# DSP_FPGA.net
KiCad netlist of a schematic drawn in Altium Designer
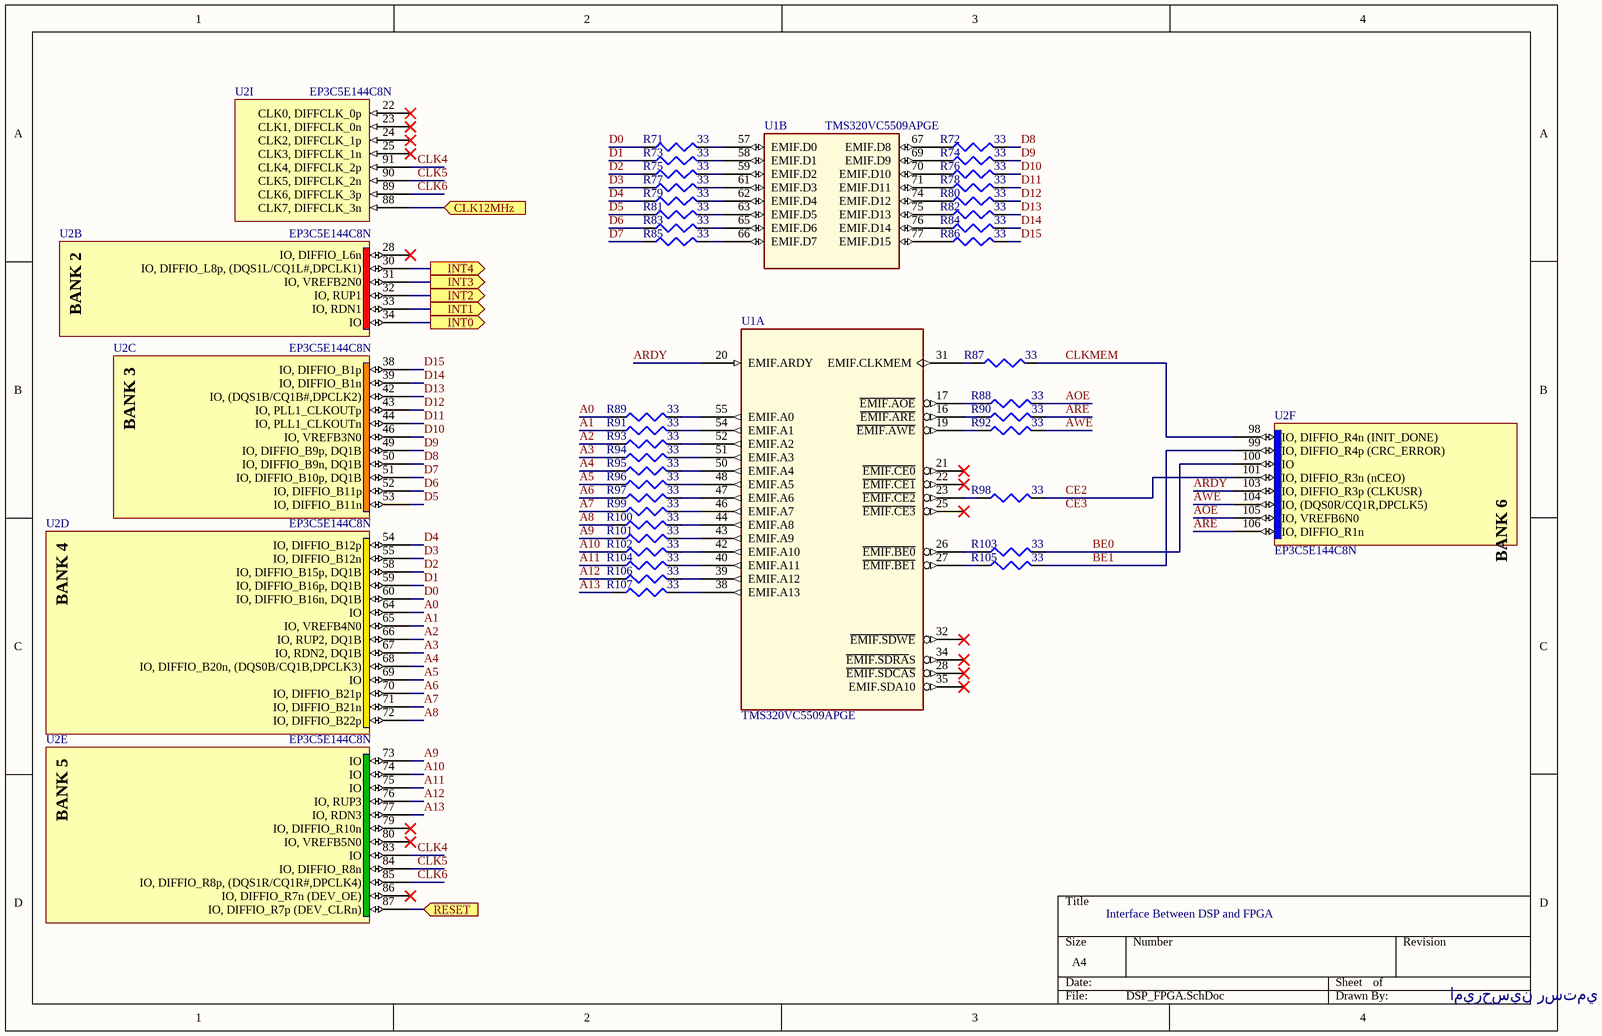
[diagram p0: DSP_FPGA.SchDoc]

(export (version "E")
  (design (tool "Eeschema 10.0.6"))
  (components
    (comp (ref "R71")
      (value "33")
      (footprint "J1-0603")
      (description "Resistor")
      (fields (field (name "PUBLISHER") "Altium Limited"))
      (libsource (lib "Miscellaneous Devices") (part "Res3"))
    )
    (comp (ref "R72")
      (value "33")
      (footprint "J1-0603")
      (description "Resistor")
      (fields (field (name "PUBLISHER") "Altium Limited"))
      (libsource (lib "Miscellaneous Devices") (part "Res3"))
    )
    (comp (ref "R73")
      (value "33")
      (footprint "J1-0603")
      (description "Resistor")
      (fields (field (name "PUBLISHER") "Altium Limited"))
      (libsource (lib "Miscellaneous Devices") (part "Res3"))
    )
    (comp (ref "R74")
      (value "33")
      (footprint "J1-0603")
      (description "Resistor")
      (fields (field (name "PUBLISHER") "Altium Limited"))
      (libsource (lib "Miscellaneous Devices") (part "Res3"))
    )
    (comp (ref "R75")
      (value "33")
      (footprint "J1-0603")
      (description "Resistor")
      (fields (field (name "PUBLISHER") "Altium Limited"))
      (libsource (lib "Miscellaneous Devices") (part "Res3"))
    )
    (comp (ref "R76")
      (value "33")
      (footprint "J1-0603")
      (description "Resistor")
      (fields (field (name "PUBLISHER") "Altium Limited"))
      (libsource (lib "Miscellaneous Devices") (part "Res3"))
    )
    (comp (ref "R77")
      (value "33")
      (footprint "J1-0603")
      (description "Resistor")
      (fields (field (name "PUBLISHER") "Altium Limited"))
      (libsource (lib "Miscellaneous Devices") (part "Res3"))
    )
    (comp (ref "R78")
      (value "33")
      (footprint "J1-0603")
      (description "Resistor")
      (fields (field (name "PUBLISHER") "Altium Limited"))
      (libsource (lib "Miscellaneous Devices") (part "Res3"))
    )
    (comp (ref "R79")
      (value "33")
      (footprint "J1-0603")
      (description "Resistor")
      (fields (field (name "PUBLISHER") "Altium Limited"))
      (libsource (lib "Miscellaneous Devices") (part "Res3"))
    )
    (comp (ref "R80")
      (value "33")
      (footprint "J1-0603")
      (description "Resistor")
      (fields (field (name "PUBLISHER") "Altium Limited"))
      (libsource (lib "Miscellaneous Devices") (part "Res3"))
    )
    (comp (ref "R81")
      (value "33")
      (footprint "J1-0603")
      (description "Resistor")
      (fields (field (name "PUBLISHER") "Altium Limited"))
      (libsource (lib "Miscellaneous Devices") (part "Res3"))
    )
    (comp (ref "R82")
      (value "33")
      (footprint "J1-0603")
      (description "Resistor")
      (fields (field (name "PUBLISHER") "Altium Limited"))
      (libsource (lib "Miscellaneous Devices") (part "Res3"))
    )
    (comp (ref "R83")
      (value "33")
      (footprint "J1-0603")
      (description "Resistor")
      (fields (field (name "PUBLISHER") "Altium Limited"))
      (libsource (lib "Miscellaneous Devices") (part "Res3"))
    )
    (comp (ref "R84")
      (value "33")
      (footprint "J1-0603")
      (description "Resistor")
      (fields (field (name "PUBLISHER") "Altium Limited"))
      (libsource (lib "Miscellaneous Devices") (part "Res3"))
    )
    (comp (ref "R85")
      (value "33")
      (footprint "J1-0603")
      (description "Resistor")
      (fields (field (name "PUBLISHER") "Altium Limited"))
      (libsource (lib "Miscellaneous Devices") (part "Res3"))
    )
    (comp (ref "R86")
      (value "33")
      (footprint "J1-0603")
      (description "Resistor")
      (fields (field (name "PUBLISHER") "Altium Limited"))
      (libsource (lib "Miscellaneous Devices") (part "Res3"))
    )
    (comp (ref "R87")
      (value "33")
      (footprint "J1-0603")
      (description "Resistor")
      (fields (field (name "PUBLISHER") "Altium Limited"))
      (libsource (lib "Miscellaneous Devices") (part "Res3"))
    )
    (comp (ref "R88")
      (value "33")
      (footprint "J1-0603")
      (description "Resistor")
      (fields (field (name "PUBLISHER") "Altium Limited"))
      (libsource (lib "Miscellaneous Devices") (part "Res3"))
    )
    (comp (ref "R89")
      (value "33")
      (footprint "J1-0603")
      (description "Resistor")
      (fields (field (name "PUBLISHER") "Altium Limited"))
      (libsource (lib "Miscellaneous Devices") (part "Res3"))
    )
    (comp (ref "R90")
      (value "33")
      (footprint "J1-0603")
      (description "Resistor")
      (fields (field (name "PUBLISHER") "Altium Limited"))
      (libsource (lib "Miscellaneous Devices") (part "Res3"))
    )
    (comp (ref "R91")
      (value "33")
      (footprint "J1-0603")
      (description "Resistor")
      (fields (field (name "PUBLISHER") "Altium Limited"))
      (libsource (lib "Miscellaneous Devices") (part "Res3"))
    )
    (comp (ref "R92")
      (value "33")
      (footprint "J1-0603")
      (description "Resistor")
      (fields (field (name "PUBLISHER") "Altium Limited"))
      (libsource (lib "Miscellaneous Devices") (part "Res3"))
    )
    (comp (ref "R93")
      (value "33")
      (footprint "J1-0603")
      (description "Resistor")
      (fields (field (name "PUBLISHER") "Altium Limited"))
      (libsource (lib "Miscellaneous Devices") (part "Res3"))
    )
    (comp (ref "R94")
      (value "33")
      (footprint "J1-0603")
      (description "Resistor")
      (fields (field (name "PUBLISHER") "Altium Limited"))
      (libsource (lib "Miscellaneous Devices") (part "Res3"))
    )
    (comp (ref "R95")
      (value "33")
      (footprint "J1-0603")
      (description "Resistor")
      (fields (field (name "PUBLISHER") "Altium Limited"))
      (libsource (lib "Miscellaneous Devices") (part "Res3"))
    )
    (comp (ref "R96")
      (value "33")
      (footprint "J1-0603")
      (description "Resistor")
      (fields (field (name "PUBLISHER") "Altium Limited"))
      (libsource (lib "Miscellaneous Devices") (part "Res3"))
    )
    (comp (ref "R97")
      (value "33")
      (footprint "J1-0603")
      (description "Resistor")
      (fields (field (name "PUBLISHER") "Altium Limited"))
      (libsource (lib "Miscellaneous Devices") (part "Res3"))
    )
    (comp (ref "R98")
      (value "33")
      (footprint "J1-0603")
      (description "Resistor")
      (fields (field (name "PUBLISHER") "Altium Limited"))
      (libsource (lib "Miscellaneous Devices") (part "Res3"))
    )
    (comp (ref "R99")
      (value "33")
      (footprint "J1-0603")
      (description "Resistor")
      (fields (field (name "PUBLISHER") "Altium Limited"))
      (libsource (lib "Miscellaneous Devices") (part "Res3"))
    )
    (comp (ref "R100")
      (value "33")
      (footprint "J1-0603")
      (description "Resistor")
      (fields (field (name "PUBLISHER") "Altium Limited"))
      (libsource (lib "Miscellaneous Devices") (part "Res3"))
    )
    (comp (ref "R101")
      (value "33")
      (footprint "J1-0603")
      (description "Resistor")
      (fields (field (name "PUBLISHER") "Altium Limited"))
      (libsource (lib "Miscellaneous Devices") (part "Res3"))
    )
    (comp (ref "R102")
      (value "33")
      (footprint "J1-0603")
      (description "Resistor")
      (fields (field (name "PUBLISHER") "Altium Limited"))
      (libsource (lib "Miscellaneous Devices") (part "Res3"))
    )
    (comp (ref "R103")
      (value "33")
      (footprint "J1-0603")
      (description "Resistor")
      (fields (field (name "PUBLISHER") "Altium Limited"))
      (libsource (lib "Miscellaneous Devices") (part "Res3"))
    )
    (comp (ref "R104")
      (value "33")
      (footprint "J1-0603")
      (description "Resistor")
      (fields (field (name "PUBLISHER") "Altium Limited"))
      (libsource (lib "Miscellaneous Devices") (part "Res3"))
    )
    (comp (ref "R105")
      (value "33")
      (footprint "J1-0603")
      (description "Resistor")
      (fields (field (name "PUBLISHER") "Altium Limited"))
      (libsource (lib "Miscellaneous Devices") (part "Res3"))
    )
    (comp (ref "R106")
      (value "33")
      (footprint "J1-0603")
      (description "Resistor")
      (fields (field (name "PUBLISHER") "Altium Limited"))
      (libsource (lib "Miscellaneous Devices") (part "Res3"))
    )
    (comp (ref "R107")
      (value "33")
      (footprint "J1-0603")
      (description "Resistor")
      (fields (field (name "PUBLISHER") "Altium Limited"))
      (libsource (lib "Miscellaneous Devices") (part "Res3"))
    )
    (comp (ref "U1")
      (value "TMS320VC5509APGE")
      (footprint "TMSVC5509APGA")
      (libsource (lib "TMSVC5509APGE") (part "TMS320VC5509APGE"))
    )
    (comp (ref "U2")
      (value "EP3C5E144C8N")
      (footprint "EQFP144_N")
      (fields (field (name "PUBLISHER") "Altium Limited"))
      (libsource (lib "") (part "EP3C5E144C8N_1"))
    )
  )
  (nets
    (net (code "1") (name "/A0") (class "Default")
      (node (ref "R89") (pin "2") (pinfunction "2_2") (pintype "passive"))
      (node (ref "U2") (pin "64") (pinfunction "IO_64") (pintype "bidirectional"))
    )
    (net (code "2") (name "/A1") (class "Default")
      (node (ref "R91") (pin "2") (pinfunction "2_2") (pintype "passive"))
      (node (ref "U2") (pin "65") (pinfunction "IO,_VREFB4N0_65") (pintype "bidirectional"))
    )
    (net (code "3") (name "/A2") (class "Default")
      (node (ref "R93") (pin "2") (pinfunction "2_2") (pintype "passive"))
      (node (ref "U2") (pin "66") (pinfunction "IO,_RUP2,_DQ1B_66") (pintype "bidirectional"))
    )
    (net (code "4") (name "/A3") (class "Default")
      (node (ref "R94") (pin "2") (pinfunction "2_2") (pintype "passive"))
      (node (ref "U2") (pin "67") (pinfunction "IO,_RDN2,_DQ1B_67") (pintype "bidirectional"))
    )
    (net (code "5") (name "/A4") (class "Default")
      (node (ref "R95") (pin "2") (pinfunction "2_2") (pintype "passive"))
      (node (ref "U2") (pin "68") (pinfunction "IO,_DIFFIO_B20n,_(DQS0B/CQ1B,DPCLK3)_68") (pintype "bidirectional"))
    )
    (net (code "6") (name "/A5") (class "Default")
      (node (ref "R96") (pin "2") (pinfunction "2_2") (pintype "passive"))
      (node (ref "U2") (pin "69") (pinfunction "IO_69") (pintype "bidirectional"))
    )
    (net (code "7") (name "/A6") (class "Default")
      (node (ref "R97") (pin "2") (pinfunction "2_2") (pintype "passive"))
      (node (ref "U2") (pin "70") (pinfunction "IO,_DIFFIO_B21p_70") (pintype "bidirectional"))
    )
    (net (code "8") (name "/A7") (class "Default")
      (node (ref "R99") (pin "2") (pinfunction "2_2") (pintype "passive"))
      (node (ref "U2") (pin "71") (pinfunction "IO,_DIFFIO_B21n_71") (pintype "bidirectional"))
    )
    (net (code "9") (name "/A8") (class "Default")
      (node (ref "R100") (pin "2") (pinfunction "2_2") (pintype "passive"))
      (node (ref "U2") (pin "72") (pinfunction "IO,_DIFFIO_B22p_72") (pintype "bidirectional"))
    )
    (net (code "10") (name "/A9") (class "Default")
      (node (ref "R101") (pin "2") (pinfunction "2_2") (pintype "passive"))
      (node (ref "U2") (pin "73") (pinfunction "IO_73") (pintype "bidirectional"))
    )
    (net (code "11") (name "/A10") (class "Default")
      (node (ref "R102") (pin "2") (pinfunction "2_2") (pintype "passive"))
      (node (ref "U2") (pin "74") (pinfunction "IO_74") (pintype "bidirectional"))
    )
    (net (code "12") (name "/A11") (class "Default")
      (node (ref "R104") (pin "2") (pinfunction "2_2") (pintype "passive"))
      (node (ref "U2") (pin "75") (pinfunction "IO_75") (pintype "bidirectional"))
    )
    (net (code "13") (name "/A12") (class "Default")
      (node (ref "R106") (pin "2") (pinfunction "2_2") (pintype "passive"))
      (node (ref "U2") (pin "76") (pinfunction "IO,_RUP3_76") (pintype "bidirectional"))
    )
    (net (code "14") (name "/A13") (class "Default")
      (node (ref "R107") (pin "2") (pinfunction "2_2") (pintype "passive"))
      (node (ref "U2") (pin "77") (pinfunction "IO,_RDN3_77") (pintype "bidirectional"))
    )
    (net (code "15") (name "/AOE") (class "Default")
      (node (ref "R88") (pin "1") (pinfunction "1_1") (pintype "passive"))
      (node (ref "U2") (pin "105") (pinfunction "IO,_VREFB6N0_105") (pintype "bidirectional"))
    )
    (net (code "16") (name "/ARDY") (class "Default")
      (node (ref "U1") (pin "20") (pinfunction "EMIF.ARDY_20") (pintype "input"))
      (node (ref "U2") (pin "103") (pinfunction "IO,_DIFFIO_R3p_(CLKUSR)_103") (pintype "bidirectional"))
    )
    (net (code "17") (name "/ARE") (class "Default")
      (node (ref "R90") (pin "1") (pinfunction "1_1") (pintype "passive"))
      (node (ref "U2") (pin "106") (pinfunction "IO,_DIFFIO_R1n_106") (pintype "bidirectional"))
    )
    (net (code "18") (name "/AWE") (class "Default")
      (node (ref "R92") (pin "1") (pinfunction "1_1") (pintype "passive"))
      (node (ref "U2") (pin "104") (pinfunction "IO,_(DQS0R/CQ1R,DPCLK5)_104") (pintype "bidirectional"))
    )
    (net (code "19") (name "/BE0") (class "Default")
      (node (ref "R103") (pin "1") (pinfunction "1_1") (pintype "passive"))
      (node (ref "U2") (pin "100") (pinfunction "IO_100") (pintype "bidirectional"))
    )
    (net (code "20") (name "/BE1") (class "Default")
      (node (ref "R105") (pin "1") (pinfunction "1_1") (pintype "passive"))
      (node (ref "U2") (pin "99") (pinfunction "IO,_DIFFIO_R4p_(CRC_ERROR)_99") (pintype "bidirectional"))
    )
    (net (code "21") (name "/CE2") (class "Default")
      (node (ref "R98") (pin "1") (pinfunction "1_1") (pintype "passive"))
      (node (ref "U2") (pin "101") (pinfunction "IO,_DIFFIO_R3n_(nCEO)_101") (pintype "bidirectional"))
    )
    (net (code "23") (name "/CLK4") (class "Default")
      (node (ref "U2") (pin "83") (pinfunction "IO_83") (pintype "bidirectional"))
      (node (ref "U2") (pin "91") (pinfunction "CLK4,_DIFFCLK_2p_91") (pintype "input"))
    )
    (net (code "24") (name "/CLK5") (class "Default")
      (node (ref "U2") (pin "84") (pinfunction "IO,_DIFFIO_R8n_84") (pintype "bidirectional"))
      (node (ref "U2") (pin "90") (pinfunction "CLK5,_DIFFCLK_2n_90") (pintype "input"))
    )
    (net (code "25") (name "/CLK6") (class "Default")
      (node (ref "U2") (pin "85") (pinfunction "IO,_DIFFIO_R8p,_(DQS1R/CQ1R#,DPCLK4)_85") (pintype "bidirectional"))
      (node (ref "U2") (pin "89") (pinfunction "CLK6,_DIFFCLK_3p_89") (pintype "input"))
    )
    (net (code "26") (name "/CLK12MHz") (class "Default")
      (node (ref "U2") (pin "88") (pinfunction "CLK7,_DIFFCLK_3n_88") (pintype "input"))
    )
    (net (code "27") (name "/CLKMEM") (class "Default")
      (node (ref "R87") (pin "1") (pinfunction "1_1") (pintype "passive"))
      (node (ref "U2") (pin "98") (pinfunction "IO,_DIFFIO_R4n_(INIT_DONE)_98") (pintype "bidirectional"))
    )
    (net (code "28") (name "/D0") (class "Default")
      (node (ref "R71") (pin "1") (pinfunction "1_1") (pintype "passive"))
      (node (ref "U2") (pin "60") (pinfunction "IO,_DIFFIO_B16n,_DQ1B_60") (pintype "bidirectional"))
    )
    (net (code "29") (name "/D1") (class "Default")
      (node (ref "R73") (pin "1") (pinfunction "1_1") (pintype "passive"))
      (node (ref "U2") (pin "59") (pinfunction "IO,_DIFFIO_B16p,_DQ1B_59") (pintype "bidirectional"))
    )
    (net (code "30") (name "/D2") (class "Default")
      (node (ref "R75") (pin "1") (pinfunction "1_1") (pintype "passive"))
      (node (ref "U2") (pin "58") (pinfunction "IO,_DIFFIO_B15p,_DQ1B_58") (pintype "bidirectional"))
    )
    (net (code "31") (name "/D3") (class "Default")
      (node (ref "R77") (pin "1") (pinfunction "1_1") (pintype "passive"))
      (node (ref "U2") (pin "55") (pinfunction "IO,_DIFFIO_B12n_55") (pintype "bidirectional"))
    )
    (net (code "32") (name "/D4") (class "Default")
      (node (ref "R79") (pin "1") (pinfunction "1_1") (pintype "passive"))
      (node (ref "U2") (pin "54") (pinfunction "IO,_DIFFIO_B12p_54") (pintype "bidirectional"))
    )
    (net (code "33") (name "/D5") (class "Default")
      (node (ref "R81") (pin "1") (pinfunction "1_1") (pintype "passive"))
      (node (ref "U2") (pin "53") (pinfunction "IO,_DIFFIO_B11n_53") (pintype "bidirectional"))
    )
    (net (code "34") (name "/D6") (class "Default")
      (node (ref "R83") (pin "1") (pinfunction "1_1") (pintype "passive"))
      (node (ref "U2") (pin "52") (pinfunction "IO,_DIFFIO_B11p_52") (pintype "bidirectional"))
    )
    (net (code "35") (name "/D7") (class "Default")
      (node (ref "R85") (pin "1") (pinfunction "1_1") (pintype "passive"))
      (node (ref "U2") (pin "51") (pinfunction "IO,_DIFFIO_B10p,_DQ1B_51") (pintype "bidirectional"))
    )
    (net (code "36") (name "/D8") (class "Default")
      (node (ref "R72") (pin "2") (pinfunction "2_2") (pintype "passive"))
      (node (ref "U2") (pin "50") (pinfunction "IO,_DIFFIO_B9n,_DQ1B_50") (pintype "bidirectional"))
    )
    (net (code "37") (name "/D9") (class "Default")
      (node (ref "R74") (pin "2") (pinfunction "2_2") (pintype "passive"))
      (node (ref "U2") (pin "49") (pinfunction "IO,_DIFFIO_B9p,_DQ1B_49") (pintype "bidirectional"))
    )
    (net (code "38") (name "/D10") (class "Default")
      (node (ref "R76") (pin "2") (pinfunction "2_2") (pintype "passive"))
      (node (ref "U2") (pin "46") (pinfunction "IO,_VREFB3N0_46") (pintype "bidirectional"))
    )
    (net (code "39") (name "/D11") (class "Default")
      (node (ref "R78") (pin "2") (pinfunction "2_2") (pintype "passive"))
      (node (ref "U2") (pin "44") (pinfunction "IO,_PLL1_CLKOUTn_44") (pintype "bidirectional"))
    )
    (net (code "40") (name "/D12") (class "Default")
      (node (ref "R80") (pin "2") (pinfunction "2_2") (pintype "passive"))
      (node (ref "U2") (pin "43") (pinfunction "IO,_PLL1_CLKOUTp_43") (pintype "bidirectional"))
    )
    (net (code "41") (name "/D13") (class "Default")
      (node (ref "R82") (pin "2") (pinfunction "2_2") (pintype "passive"))
      (node (ref "U2") (pin "42") (pinfunction "IO,_(DQS1B/CQ1B#,DPCLK2)_42") (pintype "bidirectional"))
    )
    (net (code "42") (name "/D14") (class "Default")
      (node (ref "R84") (pin "2") (pinfunction "2_2") (pintype "passive"))
      (node (ref "U2") (pin "39") (pinfunction "IO,_DIFFIO_B1n_39") (pintype "bidirectional"))
    )
    (net (code "43") (name "/D15") (class "Default")
      (node (ref "R86") (pin "2") (pinfunction "2_2") (pintype "passive"))
      (node (ref "U2") (pin "38") (pinfunction "IO,_DIFFIO_B1p_38") (pintype "bidirectional"))
    )
    (net (code "44") (name "/INT0") (class "Default")
      (node (ref "U2") (pin "34") (pinfunction "IO_34") (pintype "bidirectional"))
    )
    (net (code "45") (name "/INT1") (class "Default")
      (node (ref "U2") (pin "33") (pinfunction "IO,_RDN1_33") (pintype "bidirectional"))
    )
    (net (code "46") (name "/INT2") (class "Default")
      (node (ref "U2") (pin "32") (pinfunction "IO,_RUP1_32") (pintype "bidirectional"))
    )
    (net (code "47") (name "/INT3") (class "Default")
      (node (ref "U2") (pin "31") (pinfunction "IO,_VREFB2N0_31") (pintype "bidirectional"))
    )
    (net (code "48") (name "/INT4") (class "Default")
      (node (ref "U2") (pin "30") (pinfunction "IO,_DIFFIO_L8p,_(DQS1L/CQ1L#,DPCLK1)_30") (pintype "bidirectional"))
    )
    (net (code "49") (name "/RESET") (class "Default")
      (node (ref "U2") (pin "87") (pinfunction "IO,_DIFFIO_R7p_(DEV_CLRn)_87") (pintype "bidirectional"))
    )
    (net (code "50") (name "Net-(U1A-EMIF.A0)") (class "Default")
      (node (ref "R89") (pin "1") (pinfunction "1_1") (pintype "passive"))
      (node (ref "U1") (pin "55") (pinfunction "EMIF.A0_55") (pintype "output"))
    )
    (net (code "51") (name "Net-(U1A-EMIF.A1)") (class "Default")
      (node (ref "R91") (pin "1") (pinfunction "1_1") (pintype "passive"))
      (node (ref "U1") (pin "54") (pinfunction "EMIF.A1_54") (pintype "output"))
    )
    (net (code "52") (name "Net-(U1A-EMIF.A2)") (class "Default")
      (node (ref "R93") (pin "1") (pinfunction "1_1") (pintype "passive"))
      (node (ref "U1") (pin "52") (pinfunction "EMIF.A2_52") (pintype "output"))
    )
    (net (code "53") (name "Net-(U1A-EMIF.A3)") (class "Default")
      (node (ref "R94") (pin "1") (pinfunction "1_1") (pintype "passive"))
      (node (ref "U1") (pin "51") (pinfunction "EMIF.A3_51") (pintype "output"))
    )
    (net (code "54") (name "Net-(U1A-EMIF.A4)") (class "Default")
      (node (ref "R95") (pin "1") (pinfunction "1_1") (pintype "passive"))
      (node (ref "U1") (pin "50") (pinfunction "EMIF.A4_50") (pintype "output"))
    )
    (net (code "55") (name "Net-(U1A-EMIF.A5)") (class "Default")
      (node (ref "R96") (pin "1") (pinfunction "1_1") (pintype "passive"))
      (node (ref "U1") (pin "48") (pinfunction "EMIF.A5_48") (pintype "output"))
    )
    (net (code "56") (name "Net-(U1A-EMIF.A6)") (class "Default")
      (node (ref "R97") (pin "1") (pinfunction "1_1") (pintype "passive"))
      (node (ref "U1") (pin "47") (pinfunction "EMIF.A6_47") (pintype "output"))
    )
    (net (code "57") (name "Net-(U1A-EMIF.A7)") (class "Default")
      (node (ref "R99") (pin "1") (pinfunction "1_1") (pintype "passive"))
      (node (ref "U1") (pin "46") (pinfunction "EMIF.A7_46") (pintype "output"))
    )
    (net (code "58") (name "Net-(U1A-EMIF.A8)") (class "Default")
      (node (ref "R100") (pin "1") (pinfunction "1_1") (pintype "passive"))
      (node (ref "U1") (pin "44") (pinfunction "EMIF.A8_44") (pintype "output"))
    )
    (net (code "59") (name "Net-(U1A-EMIF.A9)") (class "Default")
      (node (ref "R101") (pin "1") (pinfunction "1_1") (pintype "passive"))
      (node (ref "U1") (pin "43") (pinfunction "EMIF.A9_43") (pintype "output"))
    )
    (net (code "60") (name "Net-(U1A-EMIF.A10)") (class "Default")
      (node (ref "R102") (pin "1") (pinfunction "1_1") (pintype "passive"))
      (node (ref "U1") (pin "42") (pinfunction "EMIF.A10_42") (pintype "output"))
    )
    (net (code "61") (name "Net-(U1A-EMIF.A11)") (class "Default")
      (node (ref "R104") (pin "1") (pinfunction "1_1") (pintype "passive"))
      (node (ref "U1") (pin "40") (pinfunction "EMIF.A11_40") (pintype "output"))
    )
    (net (code "62") (name "Net-(U1A-EMIF.A12)") (class "Default")
      (node (ref "R106") (pin "1") (pinfunction "1_1") (pintype "passive"))
      (node (ref "U1") (pin "39") (pinfunction "EMIF.A12_39") (pintype "output"))
    )
    (net (code "63") (name "Net-(U1A-EMIF.A13)") (class "Default")
      (node (ref "R107") (pin "1") (pinfunction "1_1") (pintype "passive"))
      (node (ref "U1") (pin "38") (pinfunction "EMIF.A13_38") (pintype "output"))
    )
    (net (code "64") (name "Net-(U1A-EMIF.CLKMEM)") (class "Default")
      (node (ref "R87") (pin "2") (pinfunction "2_2") (pintype "passive"))
      (node (ref "U1") (pin "31") (pinfunction "EMIF.CLKMEM_31") (pintype "output"))
    )
    (net (code "65") (name "Net-(U1A-~{EMIF.AOE})") (class "Default")
      (node (ref "R88") (pin "2") (pinfunction "2_2") (pintype "passive"))
      (node (ref "U1") (pin "17") (pinfunction "~{EMIF.AOE}_17") (pintype "output"))
    )
    (net (code "66") (name "Net-(U1A-~{EMIF.ARE})") (class "Default")
      (node (ref "R90") (pin "2") (pinfunction "2_2") (pintype "passive"))
      (node (ref "U1") (pin "16") (pinfunction "~{EMIF.ARE}_16") (pintype "output"))
    )
    (net (code "67") (name "Net-(U1A-~{EMIF.AWE})") (class "Default")
      (node (ref "R92") (pin "2") (pinfunction "2_2") (pintype "passive"))
      (node (ref "U1") (pin "19") (pinfunction "~{EMIF.AWE}_19") (pintype "output"))
    )
    (net (code "68") (name "Net-(U1A-~{EMIF.BE0})") (class "Default")
      (node (ref "R103") (pin "2") (pinfunction "2_2") (pintype "passive"))
      (node (ref "U1") (pin "26") (pinfunction "~{EMIF.BE0}_26") (pintype "output"))
    )
    (net (code "69") (name "Net-(U1A-~{EMIF.BE1})") (class "Default")
      (node (ref "R105") (pin "2") (pinfunction "2_2") (pintype "passive"))
      (node (ref "U1") (pin "27") (pinfunction "~{EMIF.BE1}_27") (pintype "output"))
    )
    (net (code "70") (name "Net-(U1A-~{EMIF.CE2})") (class "Default")
      (node (ref "R98") (pin "2") (pinfunction "2_2") (pintype "passive"))
      (node (ref "U1") (pin "23") (pinfunction "~{EMIF.CE2}_23") (pintype "output"))
    )
    (net (code "71") (name "Net-(U1B-EMIF.D0)") (class "Default")
      (node (ref "R71") (pin "2") (pinfunction "2_2") (pintype "passive"))
      (node (ref "U1") (pin "57") (pinfunction "EMIF.D0_57") (pintype "bidirectional"))
    )
    (net (code "72") (name "Net-(U1B-EMIF.D1)") (class "Default")
      (node (ref "R73") (pin "2") (pinfunction "2_2") (pintype "passive"))
      (node (ref "U1") (pin "58") (pinfunction "EMIF.D1_58") (pintype "bidirectional"))
    )
    (net (code "73") (name "Net-(U1B-EMIF.D2)") (class "Default")
      (node (ref "R75") (pin "2") (pinfunction "2_2") (pintype "passive"))
      (node (ref "U1") (pin "59") (pinfunction "EMIF.D2_59") (pintype "bidirectional"))
    )
    (net (code "74") (name "Net-(U1B-EMIF.D3)") (class "Default")
      (node (ref "R77") (pin "2") (pinfunction "2_2") (pintype "passive"))
      (node (ref "U1") (pin "61") (pinfunction "EMIF.D3_61") (pintype "bidirectional"))
    )
    (net (code "75") (name "Net-(U1B-EMIF.D4)") (class "Default")
      (node (ref "R79") (pin "2") (pinfunction "2_2") (pintype "passive"))
      (node (ref "U1") (pin "62") (pinfunction "EMIF.D4_62") (pintype "bidirectional"))
    )
    (net (code "76") (name "Net-(U1B-EMIF.D5)") (class "Default")
      (node (ref "R81") (pin "2") (pinfunction "2_2") (pintype "passive"))
      (node (ref "U1") (pin "63") (pinfunction "EMIF.D5_63") (pintype "bidirectional"))
    )
    (net (code "77") (name "Net-(U1B-EMIF.D6)") (class "Default")
      (node (ref "R83") (pin "2") (pinfunction "2_2") (pintype "passive"))
      (node (ref "U1") (pin "65") (pinfunction "EMIF.D6_65") (pintype "bidirectional"))
    )
    (net (code "78") (name "Net-(U1B-EMIF.D7)") (class "Default")
      (node (ref "R85") (pin "2") (pinfunction "2_2") (pintype "passive"))
      (node (ref "U1") (pin "66") (pinfunction "EMIF.D7_66") (pintype "bidirectional"))
    )
    (net (code "79") (name "Net-(U1B-EMIF.D8)") (class "Default")
      (node (ref "R72") (pin "1") (pinfunction "1_1") (pintype "passive"))
      (node (ref "U1") (pin "67") (pinfunction "EMIF.D8_67") (pintype "bidirectional"))
    )
    (net (code "80") (name "Net-(U1B-EMIF.D9)") (class "Default")
      (node (ref "R74") (pin "1") (pinfunction "1_1") (pintype "passive"))
      (node (ref "U1") (pin "69") (pinfunction "EMIF.D9_69") (pintype "bidirectional"))
    )
    (net (code "81") (name "Net-(U1B-EMIF.D10)") (class "Default")
      (node (ref "R76") (pin "1") (pinfunction "1_1") (pintype "passive"))
      (node (ref "U1") (pin "70") (pinfunction "EMIF.D10_70") (pintype "bidirectional"))
    )
    (net (code "82") (name "Net-(U1B-EMIF.D11)") (class "Default")
      (node (ref "R78") (pin "1") (pinfunction "1_1") (pintype "passive"))
      (node (ref "U1") (pin "71") (pinfunction "EMIF.D11_71") (pintype "bidirectional"))
    )
    (net (code "83") (name "Net-(U1B-EMIF.D12)") (class "Default")
      (node (ref "R80") (pin "1") (pinfunction "1_1") (pintype "passive"))
      (node (ref "U1") (pin "74") (pinfunction "EMIF.D12_74") (pintype "bidirectional"))
    )
    (net (code "84") (name "Net-(U1B-EMIF.D13)") (class "Default")
      (node (ref "R82") (pin "1") (pinfunction "1_1") (pintype "passive"))
      (node (ref "U1") (pin "75") (pinfunction "EMIF.D13_75") (pintype "bidirectional"))
    )
    (net (code "85") (name "Net-(U1B-EMIF.D14)") (class "Default")
      (node (ref "R84") (pin "1") (pinfunction "1_1") (pintype "passive"))
      (node (ref "U1") (pin "76") (pinfunction "EMIF.D14_76") (pintype "bidirectional"))
    )
    (net (code "86") (name "Net-(U1B-EMIF.D15)") (class "Default")
      (node (ref "R86") (pin "1") (pinfunction "1_1") (pintype "passive"))
      (node (ref "U1") (pin "77") (pinfunction "EMIF.D15_77") (pintype "bidirectional"))
    )
    (net (code "87") (name "unconnected-(U1A-EMIF.SDA10-Pad35)") (class "Default")
      (node (ref "U1") (pin "35") (pinfunction "EMIF.SDA10_35") (pintype "output+no_connect"))
    )
    (net (code "88") (name "unconnected-(U1A-~{EMIF.CE0}-Pad21)") (class "Default")
      (node (ref "U1") (pin "21") (pinfunction "~{EMIF.CE0}_21") (pintype "output+no_connect"))
    )
    (net (code "89") (name "unconnected-(U1A-~{EMIF.CE1}-Pad22)") (class "Default")
      (node (ref "U1") (pin "22") (pinfunction "~{EMIF.CE1}_22") (pintype "output+no_connect"))
    )
    (net (code "90") (name "unconnected-(U1A-~{EMIF.CE3}-Pad25)") (class "Default")
      (node (ref "U1") (pin "25") (pinfunction "~{EMIF.CE3}_25") (pintype "output+no_connect"))
    )
    (net (code "91") (name "unconnected-(U1A-~{EMIF.SDCAS}-Pad28)") (class "Default")
      (node (ref "U1") (pin "28") (pinfunction "~{EMIF.SDCAS}_28") (pintype "output+no_connect"))
    )
    (net (code "92") (name "unconnected-(U1A-~{EMIF.SDRA}S-Pad34)") (class "Default")
      (node (ref "U1") (pin "34") (pinfunction "~{EMIF.SDRA}S_34") (pintype "output+no_connect"))
    )
    (net (code "93") (name "unconnected-(U1A-~{EMIF.SDWE}-Pad32)") (class "Default")
      (node (ref "U1") (pin "32") (pinfunction "~{EMIF.SDWE}_32") (pintype "output+no_connect"))
    )
    (net (code "94") (name "unconnected-(U2B-IO,_DIFFIO_L6n-Pad28)") (class "Default")
      (node (ref "U2") (pin "28") (pinfunction "IO,_DIFFIO_L6n_28") (pintype "bidirectional+no_connect"))
    )
    (net (code "95") (name "unconnected-(U2E-IO,_DIFFIO_R7n_(DEV_OE)-Pad86)") (class "Default")
      (node (ref "U2") (pin "86") (pinfunction "IO,_DIFFIO_R7n_(DEV_OE)_86") (pintype "bidirectional+no_connect"))
    )
    (net (code "96") (name "unconnected-(U2E-IO,_DIFFIO_R10n-Pad79)") (class "Default")
      (node (ref "U2") (pin "79") (pinfunction "IO,_DIFFIO_R10n_79") (pintype "bidirectional+no_connect"))
    )
    (net (code "97") (name "unconnected-(U2E-IO,_VREFB5N0-Pad80)") (class "Default")
      (node (ref "U2") (pin "80") (pinfunction "IO,_VREFB5N0_80") (pintype "bidirectional+no_connect"))
    )
    (net (code "98") (name "unconnected-(U2I-CLK0,_DIFFCLK_0p-Pad22)") (class "Default")
      (node (ref "U2") (pin "22") (pinfunction "CLK0,_DIFFCLK_0p_22") (pintype "input+no_connect"))
    )
    (net (code "99") (name "unconnected-(U2I-CLK1,_DIFFCLK_0n-Pad23)") (class "Default")
      (node (ref "U2") (pin "23") (pinfunction "CLK1,_DIFFCLK_0n_23") (pintype "input+no_connect"))
    )
    (net (code "100") (name "unconnected-(U2I-CLK2,_DIFFCLK_1p-Pad24)") (class "Default")
      (node (ref "U2") (pin "24") (pinfunction "CLK2,_DIFFCLK_1p_24") (pintype "input+no_connect"))
    )
    (net (code "101") (name "unconnected-(U2I-CLK3,_DIFFCLK_1n-Pad25)") (class "Default")
      (node (ref "U2") (pin "25") (pinfunction "CLK3,_DIFFCLK_1n_25") (pintype "input+no_connect"))
    )
  )
)
